# PICKIT4-adaptorUPDI.net
KiCad netlist of a schematic drawn in EAGLE
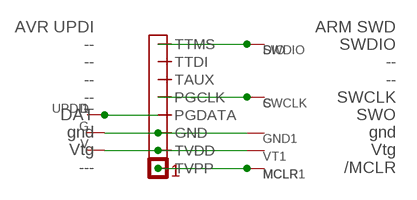
[diagram p0: schematic, sheet 1]

(export (version "E")
  (design (tool "Eeschema 10.0.6"))
  (components
    (comp (ref "C")
      (value "WIRER")
      (footprint "eagle-import:GENERIC-RD-1")
      (libsource (lib "eagle-import") (part "WIRER"))
    )
    (comp (ref "D")
      (value "WIRER")
      (footprint "eagle-import:GENERIC-RD-1")
      (libsource (lib "eagle-import") (part "WIRER"))
    )
    (comp (ref "DIO")
      (value "WIRER")
      (footprint "eagle-import:GENERIC-RD-1")
      (libsource (lib "eagle-import") (part "WIRER"))
    )
    (comp (ref "G")
      (value "WIRER")
      (footprint "eagle-import:GENERIC-RD-1")
      (libsource (lib "eagle-import") (part "WIRER"))
    )
    (comp (ref "GND1")
      (value "WIRE-R12")
      (footprint "eagle-import:VIA12")
      (libsource (lib "eagle-import") (part "WIRE-R12"))
    )
    (comp (ref "MCLR")
      (value "WIRE-R12")
      (footprint "eagle-import:VIA12")
      (libsource (lib "eagle-import") (part "WIRE-R12"))
    )
    (comp (ref "MCLR1")
      (value "WIRER")
      (footprint "eagle-import:GENERIC-RD-1")
      (libsource (lib "eagle-import") (part "WIRER"))
    )
    (comp (ref "SWCLK")
      (value "WIRE-R12")
      (footprint "eagle-import:VIA12")
      (libsource (lib "eagle-import") (part "WIRE-R12"))
    )
    (comp (ref "SWDIO")
      (value "WIRE-R12")
      (footprint "eagle-import:VIA12")
      (libsource (lib "eagle-import") (part "WIRE-R12"))
    )
    (comp (ref "U$1")
      (value "PICKIT4PINHDR")
      (footprint "eagle-import:PINHEAD1X8")
      (libsource (lib "eagle-import") (part "PICKIT4PINHDR"))
    )
    (comp (ref "UPDI1")
      (value "WIRE-R12")
      (footprint "eagle-import:VIA12")
      (libsource (lib "eagle-import") (part "WIRE-R12"))
    )
    (comp (ref "V")
      (value "WIRER")
      (footprint "eagle-import:GENERIC-RD-1")
      (libsource (lib "eagle-import") (part "WIRER"))
    )
    (comp (ref "VT1")
      (value "WIRE-R12")
      (footprint "eagle-import:VIA12")
      (libsource (lib "eagle-import") (part "WIRE-R12"))
    )
  )
  (nets
    (net (code "1") (name "Net-(U$1A-GND)") (class "Default")
      (node (ref "G") (pin "P$1") (pinfunction "P$1_P$1") (pintype "bidirectional"))
      (node (ref "GND1") (pin "P$1") (pinfunction "P$1_P$1") (pintype "bidirectional"))
      (node (ref "U$1") (pin "P$3") (pinfunction "GND_P$3") (pintype "power_in"))
    )
    (net (code "2") (name "Net-(U$1A-PGCLK)") (class "Default")
      (node (ref "C") (pin "P$1") (pinfunction "P$1_P$1") (pintype "bidirectional"))
      (node (ref "SWCLK") (pin "P$1") (pinfunction "P$1_P$1") (pintype "bidirectional"))
      (node (ref "U$1") (pin "P$5") (pinfunction "PGCLK_P$5") (pintype "bidirectional"))
    )
    (net (code "3") (name "Net-(U$1A-PGDATA)") (class "Default")
      (node (ref "D") (pin "P$1") (pinfunction "P$1_P$1") (pintype "bidirectional"))
      (node (ref "U$1") (pin "P$4") (pinfunction "PGDATA_P$4") (pintype "bidirectional"))
      (node (ref "UPDI1") (pin "P$1") (pinfunction "P$1_P$1") (pintype "bidirectional"))
    )
    (net (code "4") (name "Net-(U$1A-TTMS)") (class "Default")
      (node (ref "DIO") (pin "P$1") (pinfunction "P$1_P$1") (pintype "bidirectional"))
      (node (ref "SWDIO") (pin "P$1") (pinfunction "P$1_P$1") (pintype "bidirectional"))
      (node (ref "U$1") (pin "P$8") (pinfunction "TTMS_P$8") (pintype "bidirectional"))
    )
    (net (code "5") (name "Net-(U$1A-TVDD)") (class "Default")
      (node (ref "U$1") (pin "P$2") (pinfunction "TVDD_P$2") (pintype "bidirectional"))
      (node (ref "V") (pin "P$1") (pinfunction "P$1_P$1") (pintype "bidirectional"))
      (node (ref "VT1") (pin "P$1") (pinfunction "P$1_P$1") (pintype "bidirectional"))
    )
    (net (code "6") (name "Net-(U$1A-TVPP)") (class "Default")
      (node (ref "MCLR") (pin "P$1") (pinfunction "P$1_P$1") (pintype "bidirectional"))
      (node (ref "MCLR1") (pin "P$1") (pinfunction "P$1_P$1") (pintype "bidirectional"))
      (node (ref "U$1") (pin "P$1") (pinfunction "TVPP_P$1") (pintype "bidirectional"))
    )
    (net (code "7") (name "unconnected-(U$1A-TAUX-PadP$6)") (class "Default")
      (node (ref "U$1") (pin "P$6") (pinfunction "TAUX_P$6") (pintype "bidirectional"))
    )
    (net (code "8") (name "unconnected-(U$1A-TTDI-PadP$7)") (class "Default")
      (node (ref "U$1") (pin "P$7") (pinfunction "TTDI_P$7") (pintype "bidirectional"))
    )
  )
)
